# fpga-bank7-inside.net
KiCad netlist of a schematic drawn in Altium Designer
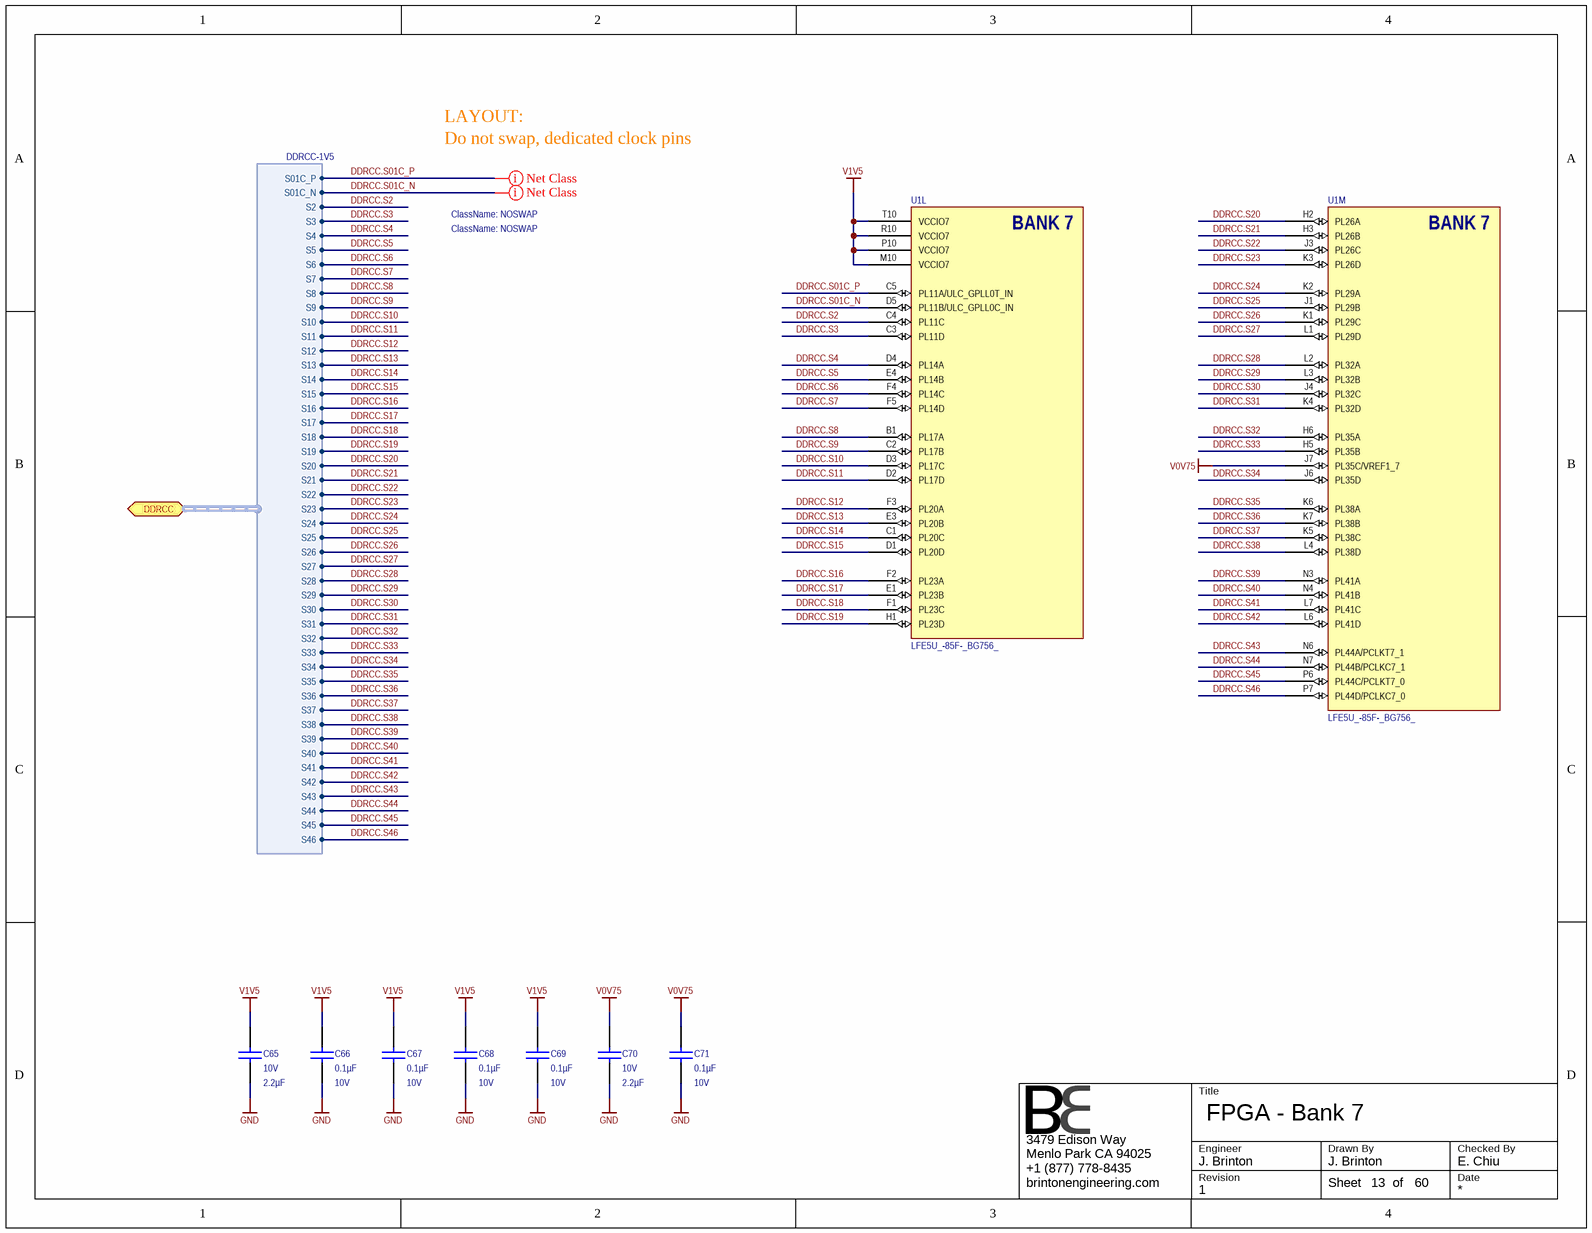
[diagram p0: fpga-bank7-inside.SchDoc]

(export (version "E")
  (design (tool "Eeschema 10.0.6"))
  (components
    (comp (ref "C65")
      (value "GRM188R71A225KE15D")
      (footprint "CAPC1608X90N")
      (description "CAP CER 2.2UF 10V 10% X7R 0603")
      (fields
        (field (name "MANUFACTURER") "Murata Electronics North America")
        (field (name "TOLERANCE") "±10%")
        (field (name "VOLTAGE - RATED") "10V")
        (field (name "CAPACITANCE") "2.2µF")
      )
      (libsource (lib "murata") (part "GRM188R71A225KE15D"))
    )
    (comp (ref "C66")
      (value "GRM155R71A104KA01J")
      (footprint "CAPC1005X56N")
      (description "CAP CER 0.1UF 10V 10% X7R 0402")
      (fields
        (field (name "MANUFACTURER") "Murata Electronics North America")
        (field (name "TOLERANCE") "±10%")
        (field (name "CAPACITANCE") "0.1µF")
        (field (name "VOLTAGE - RATED") "10V")
      )
      (libsource (lib "murata") (part "GRM155R71A104KA01J"))
    )
    (comp (ref "C67")
      (value "GRM155R71A104KA01J")
      (footprint "CAPC1005X56N")
      (description "CAP CER 0.1UF 10V 10% X7R 0402")
      (fields
        (field (name "MANUFACTURER") "Murata Electronics North America")
        (field (name "TOLERANCE") "±10%")
        (field (name "CAPACITANCE") "0.1µF")
        (field (name "VOLTAGE - RATED") "10V")
      )
      (libsource (lib "murata") (part "GRM155R71A104KA01J"))
    )
    (comp (ref "C68")
      (value "GRM155R71A104KA01J")
      (footprint "CAPC1005X56N")
      (description "CAP CER 0.1UF 10V 10% X7R 0402")
      (fields
        (field (name "MANUFACTURER") "Murata Electronics North America")
        (field (name "TOLERANCE") "±10%")
        (field (name "CAPACITANCE") "0.1µF")
        (field (name "VOLTAGE - RATED") "10V")
      )
      (libsource (lib "murata") (part "GRM155R71A104KA01J"))
    )
    (comp (ref "C69")
      (value "GRM155R71A104KA01J")
      (footprint "CAPC1005X56N")
      (description "CAP CER 0.1UF 10V 10% X7R 0402")
      (fields
        (field (name "MANUFACTURER") "Murata Electronics North America")
        (field (name "TOLERANCE") "±10%")
        (field (name "CAPACITANCE") "0.1µF")
        (field (name "VOLTAGE - RATED") "10V")
      )
      (libsource (lib "murata") (part "GRM155R71A104KA01J"))
    )
    (comp (ref "C70")
      (value "GRM188R71A225KE15D")
      (footprint "CAPC1608X90N")
      (description "CAP CER 2.2UF 10V 10% X7R 0603")
      (fields
        (field (name "MANUFACTURER") "Murata Electronics North America")
        (field (name "TOLERANCE") "±10%")
        (field (name "VOLTAGE - RATED") "10V")
        (field (name "CAPACITANCE") "2.2µF")
      )
      (libsource (lib "murata") (part "GRM188R71A225KE15D"))
    )
    (comp (ref "C71")
      (value "GRM155R71A104KA01J")
      (footprint "CAPC1005X56N")
      (description "CAP CER 0.1UF 10V 10% X7R 0402")
      (fields
        (field (name "MANUFACTURER") "Murata Electronics North America")
        (field (name "TOLERANCE") "±10%")
        (field (name "CAPACITANCE") "0.1µF")
        (field (name "VOLTAGE - RATED") "10V")
      )
      (libsource (lib "murata") (part "GRM155R71A104KA01J"))
    )
    (comp (ref "U1")
      (value "LFE5U_-85F-_BG756_")
      (footprint "lattice:caBGA756")
      (description "ECP5 FPGA, 85k LUT, 756-caBGA")
      (fields (field (name "MANUFACTURER") "Lattice Semiconductor"))
      (libsource (lib "lattice") (part "LFE5U_-85F-_BG756_"))
    )
  )
  (nets
    (net (code "2") (name "/DDRCC.S01C_N") (class "Default")
      (node (ref "U1") (pin "D5") (pinfunction "PL11B/ULC_GPLL0C_IN_D5") (pintype "bidirectional"))
    )
    (net (code "3") (name "/DDRCC.S01C_P") (class "Default")
      (node (ref "U1") (pin "C5") (pinfunction "PL11A/ULC_GPLL0T_IN_C5") (pintype "bidirectional"))
    )
    (net (code "4") (name "/DDRCC.S2") (class "Default")
      (node (ref "U1") (pin "C4") (pinfunction "PL11C_C4") (pintype "bidirectional"))
    )
    (net (code "5") (name "/DDRCC.S3") (class "Default")
      (node (ref "U1") (pin "C3") (pinfunction "PL11D_C3") (pintype "bidirectional"))
    )
    (net (code "6") (name "/DDRCC.S4") (class "Default")
      (node (ref "U1") (pin "D4") (pinfunction "PL14A_D4") (pintype "bidirectional"))
    )
    (net (code "7") (name "/DDRCC.S5") (class "Default")
      (node (ref "U1") (pin "E4") (pinfunction "PL14B_E4") (pintype "bidirectional"))
    )
    (net (code "8") (name "/DDRCC.S6") (class "Default")
      (node (ref "U1") (pin "F4") (pinfunction "PL14C_F4") (pintype "bidirectional"))
    )
    (net (code "9") (name "/DDRCC.S7") (class "Default")
      (node (ref "U1") (pin "F5") (pinfunction "PL14D_F5") (pintype "bidirectional"))
    )
    (net (code "10") (name "/DDRCC.S8") (class "Default")
      (node (ref "U1") (pin "B1") (pinfunction "PL17A_B1") (pintype "bidirectional"))
    )
    (net (code "11") (name "/DDRCC.S9") (class "Default")
      (node (ref "U1") (pin "C2") (pinfunction "PL17B_C2") (pintype "bidirectional"))
    )
    (net (code "12") (name "/DDRCC.S10") (class "Default")
      (node (ref "U1") (pin "D3") (pinfunction "PL17C_D3") (pintype "bidirectional"))
    )
    (net (code "13") (name "/DDRCC.S11") (class "Default")
      (node (ref "U1") (pin "D2") (pinfunction "PL17D_D2") (pintype "bidirectional"))
    )
    (net (code "14") (name "/DDRCC.S12") (class "Default")
      (node (ref "U1") (pin "F3") (pinfunction "PL20A_F3") (pintype "bidirectional"))
    )
    (net (code "15") (name "/DDRCC.S13") (class "Default")
      (node (ref "U1") (pin "E3") (pinfunction "PL20B_E3") (pintype "bidirectional"))
    )
    (net (code "16") (name "/DDRCC.S14") (class "Default")
      (node (ref "U1") (pin "C1") (pinfunction "PL20C_C1") (pintype "bidirectional"))
    )
    (net (code "17") (name "/DDRCC.S15") (class "Default")
      (node (ref "U1") (pin "D1") (pinfunction "PL20D_D1") (pintype "bidirectional"))
    )
    (net (code "18") (name "/DDRCC.S16") (class "Default")
      (node (ref "U1") (pin "F2") (pinfunction "PL23A_F2") (pintype "bidirectional"))
    )
    (net (code "19") (name "/DDRCC.S17") (class "Default")
      (node (ref "U1") (pin "E1") (pinfunction "PL23B_E1") (pintype "bidirectional"))
    )
    (net (code "20") (name "/DDRCC.S18") (class "Default")
      (node (ref "U1") (pin "F1") (pinfunction "PL23C_F1") (pintype "bidirectional"))
    )
    (net (code "21") (name "/DDRCC.S19") (class "Default")
      (node (ref "U1") (pin "H1") (pinfunction "PL23D_H1") (pintype "bidirectional"))
    )
    (net (code "22") (name "/DDRCC.S20") (class "Default")
      (node (ref "U1") (pin "H2") (pinfunction "PL26A_H2") (pintype "bidirectional"))
    )
    (net (code "23") (name "/DDRCC.S21") (class "Default")
      (node (ref "U1") (pin "H3") (pinfunction "PL26B_H3") (pintype "bidirectional"))
    )
    (net (code "24") (name "/DDRCC.S22") (class "Default")
      (node (ref "U1") (pin "J3") (pinfunction "PL26C_J3") (pintype "bidirectional"))
    )
    (net (code "25") (name "/DDRCC.S23") (class "Default")
      (node (ref "U1") (pin "K3") (pinfunction "PL26D_K3") (pintype "bidirectional"))
    )
    (net (code "26") (name "/DDRCC.S24") (class "Default")
      (node (ref "U1") (pin "K2") (pinfunction "PL29A_K2") (pintype "bidirectional"))
    )
    (net (code "27") (name "/DDRCC.S25") (class "Default")
      (node (ref "U1") (pin "J1") (pinfunction "PL29B_J1") (pintype "bidirectional"))
    )
    (net (code "28") (name "/DDRCC.S26") (class "Default")
      (node (ref "U1") (pin "K1") (pinfunction "PL29C_K1") (pintype "bidirectional"))
    )
    (net (code "29") (name "/DDRCC.S27") (class "Default")
      (node (ref "U1") (pin "L1") (pinfunction "PL29D_L1") (pintype "bidirectional"))
    )
    (net (code "30") (name "/DDRCC.S28") (class "Default")
      (node (ref "U1") (pin "L2") (pinfunction "PL32A_L2") (pintype "bidirectional"))
    )
    (net (code "31") (name "/DDRCC.S29") (class "Default")
      (node (ref "U1") (pin "L3") (pinfunction "PL32B_L3") (pintype "bidirectional"))
    )
    (net (code "32") (name "/DDRCC.S30") (class "Default")
      (node (ref "U1") (pin "J4") (pinfunction "PL32C_J4") (pintype "bidirectional"))
    )
    (net (code "33") (name "/DDRCC.S31") (class "Default")
      (node (ref "U1") (pin "K4") (pinfunction "PL32D_K4") (pintype "bidirectional"))
    )
    (net (code "34") (name "/DDRCC.S32") (class "Default")
      (node (ref "U1") (pin "H6") (pinfunction "PL35A_H6") (pintype "bidirectional"))
    )
    (net (code "35") (name "/DDRCC.S33") (class "Default")
      (node (ref "U1") (pin "H5") (pinfunction "PL35B_H5") (pintype "bidirectional"))
    )
    (net (code "36") (name "/DDRCC.S34") (class "Default")
      (node (ref "U1") (pin "J6") (pinfunction "PL35D_J6") (pintype "bidirectional"))
    )
    (net (code "37") (name "/DDRCC.S35") (class "Default")
      (node (ref "U1") (pin "K6") (pinfunction "PL38A_K6") (pintype "bidirectional"))
    )
    (net (code "38") (name "/DDRCC.S36") (class "Default")
      (node (ref "U1") (pin "K7") (pinfunction "PL38B_K7") (pintype "bidirectional"))
    )
    (net (code "39") (name "/DDRCC.S37") (class "Default")
      (node (ref "U1") (pin "K5") (pinfunction "PL38C_K5") (pintype "bidirectional"))
    )
    (net (code "40") (name "/DDRCC.S38") (class "Default")
      (node (ref "U1") (pin "L4") (pinfunction "PL38D_L4") (pintype "bidirectional"))
    )
    (net (code "41") (name "/DDRCC.S39") (class "Default")
      (node (ref "U1") (pin "N3") (pinfunction "PL41A_N3") (pintype "bidirectional"))
    )
    (net (code "42") (name "/DDRCC.S40") (class "Default")
      (node (ref "U1") (pin "N4") (pinfunction "PL41B_N4") (pintype "bidirectional"))
    )
    (net (code "43") (name "/DDRCC.S41") (class "Default")
      (node (ref "U1") (pin "L7") (pinfunction "PL41C_L7") (pintype "bidirectional"))
    )
    (net (code "44") (name "/DDRCC.S42") (class "Default")
      (node (ref "U1") (pin "L6") (pinfunction "PL41D_L6") (pintype "bidirectional"))
    )
    (net (code "45") (name "/DDRCC.S43") (class "Default")
      (node (ref "U1") (pin "N6") (pinfunction "PL44A/PCLKT7_1_N6") (pintype "bidirectional"))
    )
    (net (code "46") (name "/DDRCC.S44") (class "Default")
      (node (ref "U1") (pin "N7") (pinfunction "PL44B/PCLKC7_1_N7") (pintype "bidirectional"))
    )
    (net (code "47") (name "/DDRCC.S45") (class "Default")
      (node (ref "U1") (pin "P6") (pinfunction "PL44C/PCLKT7_0_P6") (pintype "bidirectional"))
    )
    (net (code "48") (name "/DDRCC.S46") (class "Default")
      (node (ref "U1") (pin "P7") (pinfunction "PL44D/PCLKC7_0_P7") (pintype "bidirectional"))
    )
    (net (code "50") (name "GND") (class "Default")
      (node (ref "C65") (pin "1") (pinfunction "1_1") (pintype "passive"))
      (node (ref "C66") (pin "1") (pinfunction "1_1") (pintype "passive"))
      (node (ref "C67") (pin "1") (pinfunction "1_1") (pintype "passive"))
      (node (ref "C68") (pin "1") (pinfunction "1_1") (pintype "passive"))
      (node (ref "C69") (pin "1") (pinfunction "1_1") (pintype "passive"))
      (node (ref "C70") (pin "1") (pinfunction "1_1") (pintype "passive"))
      (node (ref "C71") (pin "1") (pinfunction "1_1") (pintype "passive"))
    )
    (net (code "51") (name "V0V75") (class "Default")
      (node (ref "C70") (pin "2") (pinfunction "2_2") (pintype "passive"))
      (node (ref "C71") (pin "2") (pinfunction "2_2") (pintype "passive"))
      (node (ref "U1") (pin "J7") (pinfunction "PL35C/VREF1_7_J7") (pintype "bidirectional"))
    )
    (net (code "52") (name "V1V5") (class "Default")
      (node (ref "C65") (pin "2") (pinfunction "2_2") (pintype "passive"))
      (node (ref "C66") (pin "2") (pinfunction "2_2") (pintype "passive"))
      (node (ref "C67") (pin "2") (pinfunction "2_2") (pintype "passive"))
      (node (ref "C68") (pin "2") (pinfunction "2_2") (pintype "passive"))
      (node (ref "C69") (pin "2") (pinfunction "2_2") (pintype "passive"))
      (node (ref "U1") (pin "M10") (pinfunction "VCCIO7_M10") (pintype "power_in"))
      (node (ref "U1") (pin "P10") (pinfunction "VCCIO7_P10") (pintype "power_in"))
      (node (ref "U1") (pin "R10") (pinfunction "VCCIO7_R10") (pintype "power_in"))
      (node (ref "U1") (pin "T10") (pinfunction "VCCIO7_T10") (pintype "power_in"))
    )
  )
)
